# SWD_Breakout.net
KiCad netlist of a schematic drawn in Altium Designer
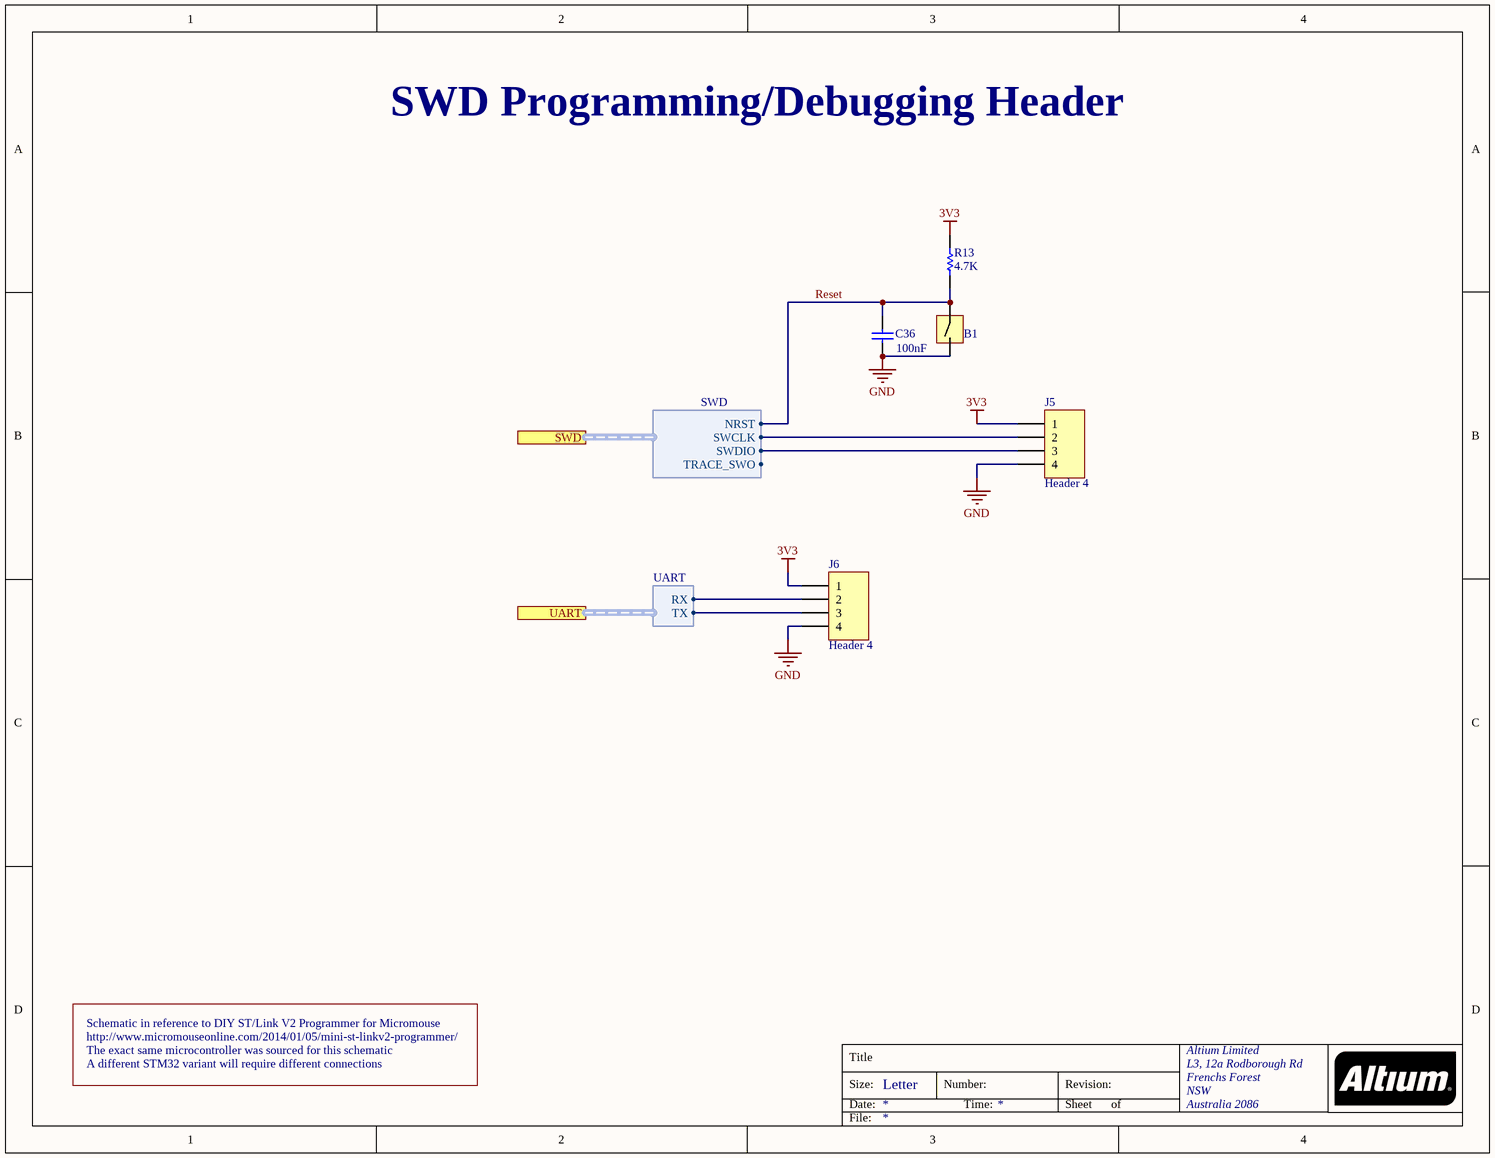
[diagram p0: SWD_Breakout.SchDoc]

(export (version "E")
  (design (tool "Eeschema 10.0.6"))
  (components
    (comp (ref "B1")
      (value "Push Button")
      (footprint "PUSHBUTTON")
      (libsource (lib "LaunchyRIOComponents") (part "PushButton"))
    )
    (comp (ref "C36")
      (value "100nF")
      (footprint "0603")
      (description "Capacitor")
      (fields (field (name "Comment") "Cap"))
      (libsource (lib "Miscellaneous Devices") (part "Cap"))
    )
    (comp (ref "J5")
      (value "Header 4")
      (footprint "HDR1X4")
      (description "Header, 4-Pin")
      (fields (field (name "PUBLISHER") "Altium Limited"))
      (libsource (lib "Miscellaneous Connectors") (part "Header 4"))
    )
    (comp (ref "J6")
      (value "Header 4")
      (footprint "HDR1X4")
      (description "Header, 4-Pin")
      (fields (field (name "PUBLISHER") "Altium Limited"))
      (libsource (lib "Miscellaneous Connectors") (part "Header 4"))
    )
    (comp (ref "R13")
      (value "4.7K")
      (footprint "0603")
      (description "Resistor")
      (fields (field (name "Comment") "Res1"))
      (libsource (lib "Miscellaneous Devices") (part "Res1"))
    )
  )
  (nets
    (net (code "3") (name "/RX") (class "Default")
      (node (ref "J6") (pin "2") (pinfunction "2_2") (pintype "passive"))
    )
    (net (code "4") (name "/Reset") (class "Default")
      (node (ref "B1") (pin "1") (pinfunction "0_1") (pintype "passive"))
      (node (ref "C36") (pin "2") (pinfunction "2_2") (pintype "passive"))
      (node (ref "R13") (pin "1") (pinfunction "1_1") (pintype "passive"))
    )
    (net (code "5") (name "/SWCLK") (class "Default")
      (node (ref "J5") (pin "2") (pinfunction "2_2") (pintype "passive"))
    )
    (net (code "6") (name "/SWDIO") (class "Default")
      (node (ref "J5") (pin "3") (pinfunction "3_3") (pintype "passive"))
    )
    (net (code "7") (name "/TX") (class "Default")
      (node (ref "J6") (pin "3") (pinfunction "3_3") (pintype "passive"))
    )
    (net (code "10") (name "3V3") (class "Default")
      (node (ref "J5") (pin "1") (pinfunction "1_1") (pintype "passive"))
      (node (ref "J6") (pin "1") (pinfunction "1_1") (pintype "passive"))
      (node (ref "R13") (pin "2") (pinfunction "2_2") (pintype "passive"))
    )
    (net (code "11") (name "GND") (class "Default")
      (node (ref "B1") (pin "2") (pinfunction "1_2") (pintype "passive"))
      (node (ref "C36") (pin "1") (pinfunction "1_1") (pintype "passive"))
      (node (ref "J5") (pin "4") (pinfunction "4_4") (pintype "passive"))
      (node (ref "J6") (pin "4") (pinfunction "4_4") (pintype "passive"))
    )
  )
)
